# SiNEDevBoard.net
KiCad netlist of a schematic drawn in EAGLE
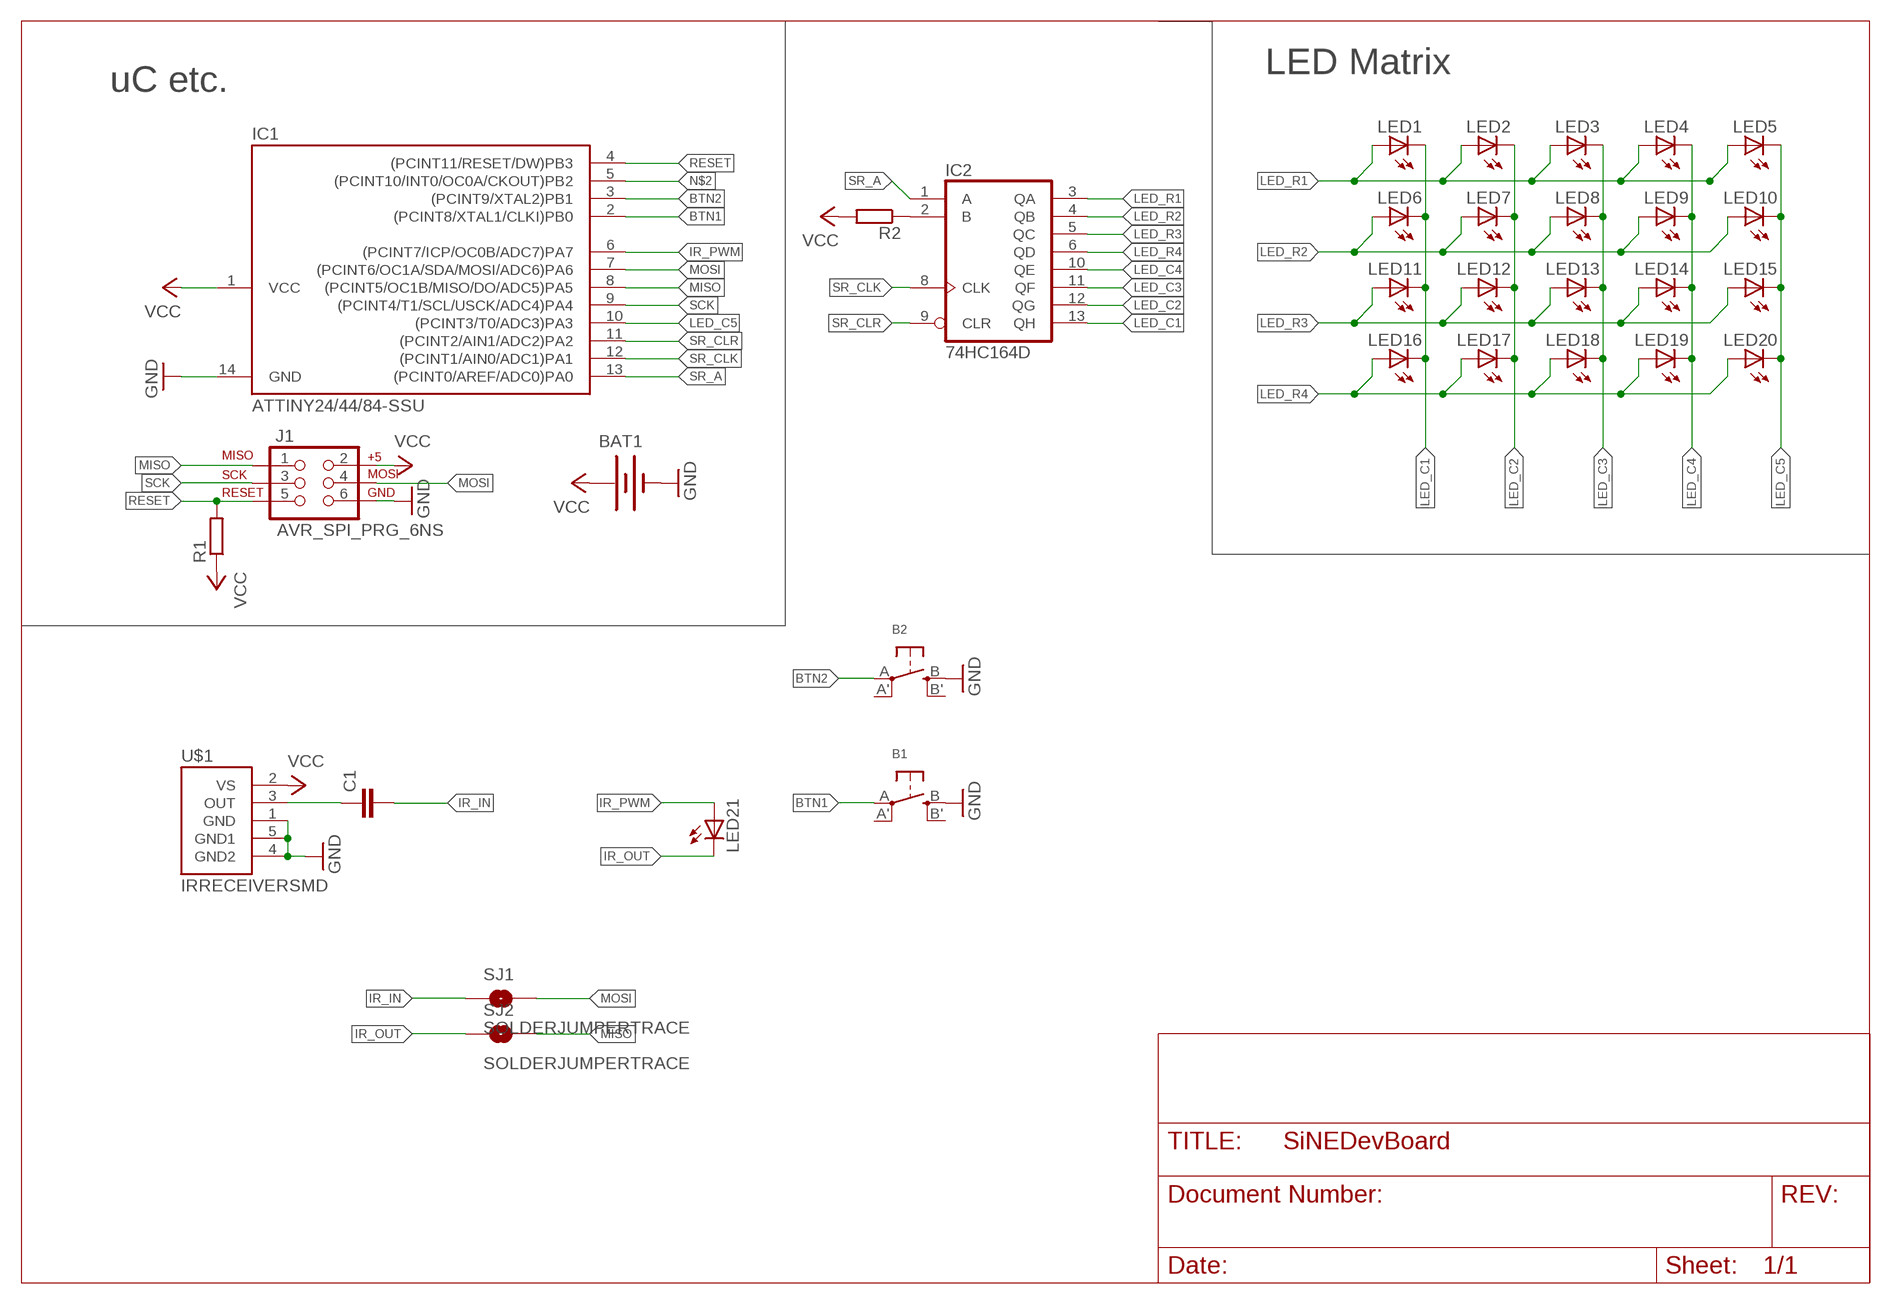
[diagram p0: schematic, sheet 1]

(export (version "E")
  (design (tool "Eeschema 10.0.6"))
  (components
    (comp (ref "B1")
      (value "SWITCH_TACT_SMT")
      (footprint "eagle-import:EVQ-Q2")
      (libsource (lib "eagle-import") (part "SWITCH_TACT_SMT"))
    )
    (comp (ref "B2")
      (value "SWITCH_TACT_SMT")
      (footprint "eagle-import:EVQ-Q2")
      (libsource (lib "eagle-import") (part "SWITCH_TACT_SMT"))
    )
    (comp (ref "BAT1")
      (value "BATTERY20SMD")
      (footprint "eagle-import:BATTCON_20MM")
      (libsource (lib "eagle-import") (part "BATTERY20SMD"))
    )
    (comp (ref "C1")
      (value "C-EUC0805")
      (footprint "eagle-import:C0805")
      (libsource (lib "eagle-import") (part "C-EUC0805"))
    )
    (comp (ref "IC1")
      (value "ATTINY24/44/84-SSU")
      (footprint "eagle-import:SOIC14")
      (libsource (lib "eagle-import") (part "ATTINY24/44/84-SSU"))
    )
    (comp (ref "IC2")
      (value "74HC164D")
      (footprint "eagle-import:SO14")
      (libsource (lib "eagle-import") (part "74164DHC"))
    )
    (comp (ref "J1")
      (value "AVR_SPI_PRG_6NS")
      (footprint "eagle-import:2X3-NS")
      (libsource (lib "eagle-import") (part "AVR_SPI_PRG_6NS"))
    )
    (comp (ref "LED1")
      (value "LEDCHIPLED_0805")
      (footprint "eagle-import:CHIPLED_0805")
      (libsource (lib "eagle-import") (part "LEDCHIPLED_0805"))
    )
    (comp (ref "LED2")
      (value "LEDCHIPLED_0805")
      (footprint "eagle-import:CHIPLED_0805")
      (libsource (lib "eagle-import") (part "LEDCHIPLED_0805"))
    )
    (comp (ref "LED3")
      (value "LEDCHIPLED_0805")
      (footprint "eagle-import:CHIPLED_0805")
      (libsource (lib "eagle-import") (part "LEDCHIPLED_0805"))
    )
    (comp (ref "LED4")
      (value "LEDCHIPLED_0805")
      (footprint "eagle-import:CHIPLED_0805")
      (libsource (lib "eagle-import") (part "LEDCHIPLED_0805"))
    )
    (comp (ref "LED5")
      (value "LEDCHIPLED_0805")
      (footprint "eagle-import:CHIPLED_0805")
      (libsource (lib "eagle-import") (part "LEDCHIPLED_0805"))
    )
    (comp (ref "LED6")
      (value "LEDCHIPLED_0805")
      (footprint "eagle-import:CHIPLED_0805")
      (libsource (lib "eagle-import") (part "LEDCHIPLED_0805"))
    )
    (comp (ref "LED7")
      (value "LEDCHIPLED_0805")
      (footprint "eagle-import:CHIPLED_0805")
      (libsource (lib "eagle-import") (part "LEDCHIPLED_0805"))
    )
    (comp (ref "LED8")
      (value "LEDCHIPLED_0805")
      (footprint "eagle-import:CHIPLED_0805")
      (libsource (lib "eagle-import") (part "LEDCHIPLED_0805"))
    )
    (comp (ref "LED9")
      (value "LEDCHIPLED_0805")
      (footprint "eagle-import:CHIPLED_0805")
      (libsource (lib "eagle-import") (part "LEDCHIPLED_0805"))
    )
    (comp (ref "LED10")
      (value "LEDCHIPLED_0805")
      (footprint "eagle-import:CHIPLED_0805")
      (libsource (lib "eagle-import") (part "LEDCHIPLED_0805"))
    )
    (comp (ref "LED11")
      (value "LEDCHIPLED_0805")
      (footprint "eagle-import:CHIPLED_0805")
      (libsource (lib "eagle-import") (part "LEDCHIPLED_0805"))
    )
    (comp (ref "LED12")
      (value "LEDCHIPLED_0805")
      (footprint "eagle-import:CHIPLED_0805")
      (libsource (lib "eagle-import") (part "LEDCHIPLED_0805"))
    )
    (comp (ref "LED13")
      (value "LEDCHIPLED_0805")
      (footprint "eagle-import:CHIPLED_0805")
      (libsource (lib "eagle-import") (part "LEDCHIPLED_0805"))
    )
    (comp (ref "LED14")
      (value "LEDCHIPLED_0805")
      (footprint "eagle-import:CHIPLED_0805")
      (libsource (lib "eagle-import") (part "LEDCHIPLED_0805"))
    )
    (comp (ref "LED15")
      (value "LEDCHIPLED_0805")
      (footprint "eagle-import:CHIPLED_0805")
      (libsource (lib "eagle-import") (part "LEDCHIPLED_0805"))
    )
    (comp (ref "LED16")
      (value "LEDCHIPLED_0805")
      (footprint "eagle-import:CHIPLED_0805")
      (libsource (lib "eagle-import") (part "LEDCHIPLED_0805"))
    )
    (comp (ref "LED17")
      (value "LEDCHIPLED_0805")
      (footprint "eagle-import:CHIPLED_0805")
      (libsource (lib "eagle-import") (part "LEDCHIPLED_0805"))
    )
    (comp (ref "LED18")
      (value "LEDCHIPLED_0805")
      (footprint "eagle-import:CHIPLED_0805")
      (libsource (lib "eagle-import") (part "LEDCHIPLED_0805"))
    )
    (comp (ref "LED19")
      (value "LEDCHIPLED_0805")
      (footprint "eagle-import:CHIPLED_0805")
      (libsource (lib "eagle-import") (part "LEDCHIPLED_0805"))
    )
    (comp (ref "LED20")
      (value "LEDCHIPLED_0805")
      (footprint "eagle-import:CHIPLED_0805")
      (libsource (lib "eagle-import") (part "LEDCHIPLED_0805"))
    )
    (comp (ref "LED21")
      (value "LEDCHIPLED_1206")
      (footprint "eagle-import:CHIPLED_1206")
      (libsource (lib "eagle-import") (part "led_LEDCHIPLED_1206"))
    )
    (comp (ref "R1")
      (value "R-EU_R0805")
      (footprint "eagle-import:R0805")
      (libsource (lib "eagle-import") (part "R-EU_R0805"))
    )
    (comp (ref "R2")
      (value "R-EU_R0805")
      (footprint "eagle-import:R0805")
      (libsource (lib "eagle-import") (part "R-EU_R0805"))
    )
    (comp (ref "SJ1")
      (value "SOLDERJUMPERTRACE")
      (footprint "eagle-import:SJ_2S-TRACE")
      (libsource (lib "eagle-import") (part "SOLDERJUMPERTRACE"))
    )
    (comp (ref "SJ2")
      (value "SOLDERJUMPERTRACE")
      (footprint "eagle-import:SJ_2S-TRACE")
      (libsource (lib "eagle-import") (part "SOLDERJUMPERTRACE"))
    )
    (comp (ref "U$1")
      (value "IRRECEIVERSMD")
      (footprint "eagle-import:TSOP8523")
      (libsource (lib "eagle-import") (part "IRRECEIVERSMD"))
    )
  )
  (nets
    (net (code "1") (name "BTN1") (class "Default")
      (node (ref "B1") (pin "A") (pinfunction "P_A") (pintype "passive"))
      (node (ref "IC1") (pin "2") (pinfunction "(PCINT8/XTAL1/CLKI)PB0_2") (pintype "bidirectional"))
    )
    (net (code "2") (name "BTN2") (class "Default")
      (node (ref "B2") (pin "A") (pinfunction "P_A") (pintype "passive"))
      (node (ref "IC1") (pin "3") (pinfunction "(PCINT9/XTAL2)PB1_3") (pintype "bidirectional"))
    )
    (net (code "3") (name "GND") (class "Default")
      (node (ref "B1") (pin "B") (pinfunction "S_B") (pintype "passive"))
      (node (ref "B2") (pin "B") (pinfunction "S_B") (pintype "passive"))
      (node (ref "BAT1") (pin "2") (pinfunction "-_2") (pintype "power_in"))
      (node (ref "IC1") (pin "14") (pinfunction "GND_14") (pintype "power_in"))
      (node (ref "J1") (pin "6") (pinfunction "6_6") (pintype "passive"))
      (node (ref "U$1") (pin "1") (pinfunction "GND_1") (pintype "bidirectional"))
      (node (ref "U$1") (pin "4") (pinfunction "GND2_4") (pintype "bidirectional"))
      (node (ref "U$1") (pin "5") (pinfunction "GND1_5") (pintype "bidirectional"))
    )
    (net (code "4") (name "IR_IN") (class "Default")
      (node (ref "C1") (pin "2") (pinfunction "2_2") (pintype "passive"))
      (node (ref "SJ1") (pin "1") (pinfunction "1_1") (pintype "passive"))
    )
    (net (code "5") (name "IR_OUT") (class "Default")
      (node (ref "LED21") (pin "C") (pinfunction "C_C") (pintype "passive"))
      (node (ref "SJ2") (pin "1") (pinfunction "1_1") (pintype "passive"))
    )
    (net (code "6") (name "IR_PWM") (class "Default")
      (node (ref "IC1") (pin "6") (pinfunction "(PCINT7/ICP/OC0B/ADC7)PA7_6") (pintype "bidirectional"))
      (node (ref "LED21") (pin "A") (pinfunction "A_A") (pintype "passive"))
    )
    (net (code "7") (name "LED_C1") (class "Default")
      (node (ref "IC2") (pin "13") (pinfunction "QH_13") (pintype "output"))
      (node (ref "LED1") (pin "C") (pinfunction "C_C") (pintype "passive"))
      (node (ref "LED11") (pin "C") (pinfunction "C_C") (pintype "passive"))
      (node (ref "LED16") (pin "C") (pinfunction "C_C") (pintype "passive"))
      (node (ref "LED6") (pin "C") (pinfunction "C_C") (pintype "passive"))
    )
    (net (code "8") (name "LED_C2") (class "Default")
      (node (ref "IC2") (pin "12") (pinfunction "QG_12") (pintype "output"))
      (node (ref "LED12") (pin "C") (pinfunction "C_C") (pintype "passive"))
      (node (ref "LED17") (pin "C") (pinfunction "C_C") (pintype "passive"))
      (node (ref "LED2") (pin "C") (pinfunction "C_C") (pintype "passive"))
      (node (ref "LED7") (pin "C") (pinfunction "C_C") (pintype "passive"))
    )
    (net (code "9") (name "LED_C3") (class "Default")
      (node (ref "IC2") (pin "11") (pinfunction "QF_11") (pintype "output"))
      (node (ref "LED13") (pin "C") (pinfunction "C_C") (pintype "passive"))
      (node (ref "LED18") (pin "C") (pinfunction "C_C") (pintype "passive"))
      (node (ref "LED3") (pin "C") (pinfunction "C_C") (pintype "passive"))
      (node (ref "LED8") (pin "C") (pinfunction "C_C") (pintype "passive"))
    )
    (net (code "10") (name "LED_C4") (class "Default")
      (node (ref "IC2") (pin "10") (pinfunction "QE_10") (pintype "output"))
      (node (ref "LED14") (pin "C") (pinfunction "C_C") (pintype "passive"))
      (node (ref "LED19") (pin "C") (pinfunction "C_C") (pintype "passive"))
      (node (ref "LED4") (pin "C") (pinfunction "C_C") (pintype "passive"))
      (node (ref "LED9") (pin "C") (pinfunction "C_C") (pintype "passive"))
    )
    (net (code "11") (name "LED_C5") (class "Default")
      (node (ref "IC1") (pin "10") (pinfunction "(PCINT3/T0/ADC3)PA3_10") (pintype "bidirectional"))
      (node (ref "LED10") (pin "C") (pinfunction "C_C") (pintype "passive"))
      (node (ref "LED15") (pin "C") (pinfunction "C_C") (pintype "passive"))
      (node (ref "LED20") (pin "C") (pinfunction "C_C") (pintype "passive"))
      (node (ref "LED5") (pin "C") (pinfunction "C_C") (pintype "passive"))
    )
    (net (code "12") (name "LED_R1") (class "Default")
      (node (ref "IC2") (pin "3") (pinfunction "QA_3") (pintype "output"))
      (node (ref "LED1") (pin "A") (pinfunction "A_A") (pintype "passive"))
      (node (ref "LED2") (pin "A") (pinfunction "A_A") (pintype "passive"))
      (node (ref "LED3") (pin "A") (pinfunction "A_A") (pintype "passive"))
      (node (ref "LED4") (pin "A") (pinfunction "A_A") (pintype "passive"))
      (node (ref "LED5") (pin "A") (pinfunction "A_A") (pintype "passive"))
    )
    (net (code "13") (name "LED_R2") (class "Default")
      (node (ref "IC2") (pin "4") (pinfunction "QB_4") (pintype "output"))
      (node (ref "LED10") (pin "A") (pinfunction "A_A") (pintype "passive"))
      (node (ref "LED6") (pin "A") (pinfunction "A_A") (pintype "passive"))
      (node (ref "LED7") (pin "A") (pinfunction "A_A") (pintype "passive"))
      (node (ref "LED8") (pin "A") (pinfunction "A_A") (pintype "passive"))
      (node (ref "LED9") (pin "A") (pinfunction "A_A") (pintype "passive"))
    )
    (net (code "14") (name "LED_R3") (class "Default")
      (node (ref "IC2") (pin "5") (pinfunction "QC_5") (pintype "output"))
      (node (ref "LED11") (pin "A") (pinfunction "A_A") (pintype "passive"))
      (node (ref "LED12") (pin "A") (pinfunction "A_A") (pintype "passive"))
      (node (ref "LED13") (pin "A") (pinfunction "A_A") (pintype "passive"))
      (node (ref "LED14") (pin "A") (pinfunction "A_A") (pintype "passive"))
      (node (ref "LED15") (pin "A") (pinfunction "A_A") (pintype "passive"))
    )
    (net (code "15") (name "LED_R4") (class "Default")
      (node (ref "IC2") (pin "6") (pinfunction "QD_6") (pintype "output"))
      (node (ref "LED16") (pin "A") (pinfunction "A_A") (pintype "passive"))
      (node (ref "LED17") (pin "A") (pinfunction "A_A") (pintype "passive"))
      (node (ref "LED18") (pin "A") (pinfunction "A_A") (pintype "passive"))
      (node (ref "LED19") (pin "A") (pinfunction "A_A") (pintype "passive"))
      (node (ref "LED20") (pin "A") (pinfunction "A_A") (pintype "passive"))
    )
    (net (code "16") (name "MISO") (class "Default")
      (node (ref "IC1") (pin "8") (pinfunction "(PCINT5/OC1B/MISO/DO/ADC5)PA5_8") (pintype "bidirectional"))
      (node (ref "J1") (pin "1") (pinfunction "1_1") (pintype "passive"))
      (node (ref "SJ2") (pin "2") (pinfunction "2_2") (pintype "passive"))
    )
    (net (code "17") (name "MOSI") (class "Default")
      (node (ref "IC1") (pin "7") (pinfunction "(PCINT6/OC1A/SDA/MOSI/ADC6)PA6_7") (pintype "bidirectional"))
      (node (ref "J1") (pin "4") (pinfunction "4_4") (pintype "passive"))
      (node (ref "SJ1") (pin "2") (pinfunction "2_2") (pintype "passive"))
    )
    (net (code "18") (name "N$2") (class "Default")
      (node (ref "IC1") (pin "5") (pinfunction "(PCINT10/INT0/OC0A/CKOUT)PB2_5") (pintype "bidirectional"))
    )
    (net (code "19") (name "Net-(IC2A-B)") (class "Default")
      (node (ref "IC2") (pin "2") (pinfunction "B_2") (pintype "input"))
      (node (ref "R2") (pin "1") (pinfunction "1_1") (pintype "passive"))
    )
    (net (code "20") (name "Net-(U$1-OUT)") (class "Default")
      (node (ref "C1") (pin "1") (pinfunction "1_1") (pintype "passive"))
      (node (ref "U$1") (pin "3") (pinfunction "OUT_3") (pintype "bidirectional"))
    )
    (net (code "21") (name "RESET") (class "Default")
      (node (ref "IC1") (pin "4") (pinfunction "(PCINT11/RESET/DW)PB3_4") (pintype "bidirectional"))
      (node (ref "J1") (pin "5") (pinfunction "5_5") (pintype "passive"))
      (node (ref "R1") (pin "2") (pinfunction "2_2") (pintype "passive"))
    )
    (net (code "22") (name "SCK") (class "Default")
      (node (ref "IC1") (pin "9") (pinfunction "(PCINT4/T1/SCL/USCK/ADC4)PA4_9") (pintype "bidirectional"))
      (node (ref "J1") (pin "3") (pinfunction "3_3") (pintype "passive"))
    )
    (net (code "23") (name "SR_A") (class "Default")
      (node (ref "IC1") (pin "13") (pinfunction "(PCINT0/AREF/ADC0)PA0_13") (pintype "bidirectional"))
      (node (ref "IC2") (pin "1") (pinfunction "A_1") (pintype "input"))
    )
    (net (code "24") (name "SR_CLK") (class "Default")
      (node (ref "IC1") (pin "12") (pinfunction "(PCINT1/AIN0/ADC1)PA1_12") (pintype "bidirectional"))
      (node (ref "IC2") (pin "8") (pinfunction "CLK_8") (pintype "input"))
    )
    (net (code "25") (name "SR_CLR") (class "Default")
      (node (ref "IC1") (pin "11") (pinfunction "(PCINT2/AIN1/ADC2)PA2_11") (pintype "bidirectional"))
      (node (ref "IC2") (pin "9") (pinfunction "CLR_9") (pintype "input"))
    )
    (net (code "26") (name "VCC") (class "Default")
      (node (ref "BAT1") (pin "1") (pinfunction "+_1") (pintype "power_in"))
      (node (ref "IC1") (pin "1") (pinfunction "VCC_1") (pintype "power_in"))
      (node (ref "J1") (pin "2") (pinfunction "2_2") (pintype "passive"))
      (node (ref "R1") (pin "1") (pinfunction "1_1") (pintype "passive"))
      (node (ref "R2") (pin "2") (pinfunction "2_2") (pintype "passive"))
      (node (ref "U$1") (pin "2") (pinfunction "VS_2") (pintype "bidirectional"))
    )
    (net (code "27") (name "unconnected-(B1-P1-PadA')") (class "Default")
      (node (ref "B1") (pin "A'") (pinfunction "P1_A'") (pintype "passive"))
    )
    (net (code "28") (name "unconnected-(B1-S1-PadB')") (class "Default")
      (node (ref "B1") (pin "B'") (pinfunction "S1_B'") (pintype "passive"))
    )
    (net (code "29") (name "unconnected-(B2-P1-PadA')") (class "Default")
      (node (ref "B2") (pin "A'") (pinfunction "P1_A'") (pintype "passive"))
    )
    (net (code "30") (name "unconnected-(B2-S1-PadB')") (class "Default")
      (node (ref "B2") (pin "B'") (pinfunction "S1_B'") (pintype "passive"))
    )
  )
)
